# Posibus.net
KiCad netlist of a schematic drawn in EAGLE
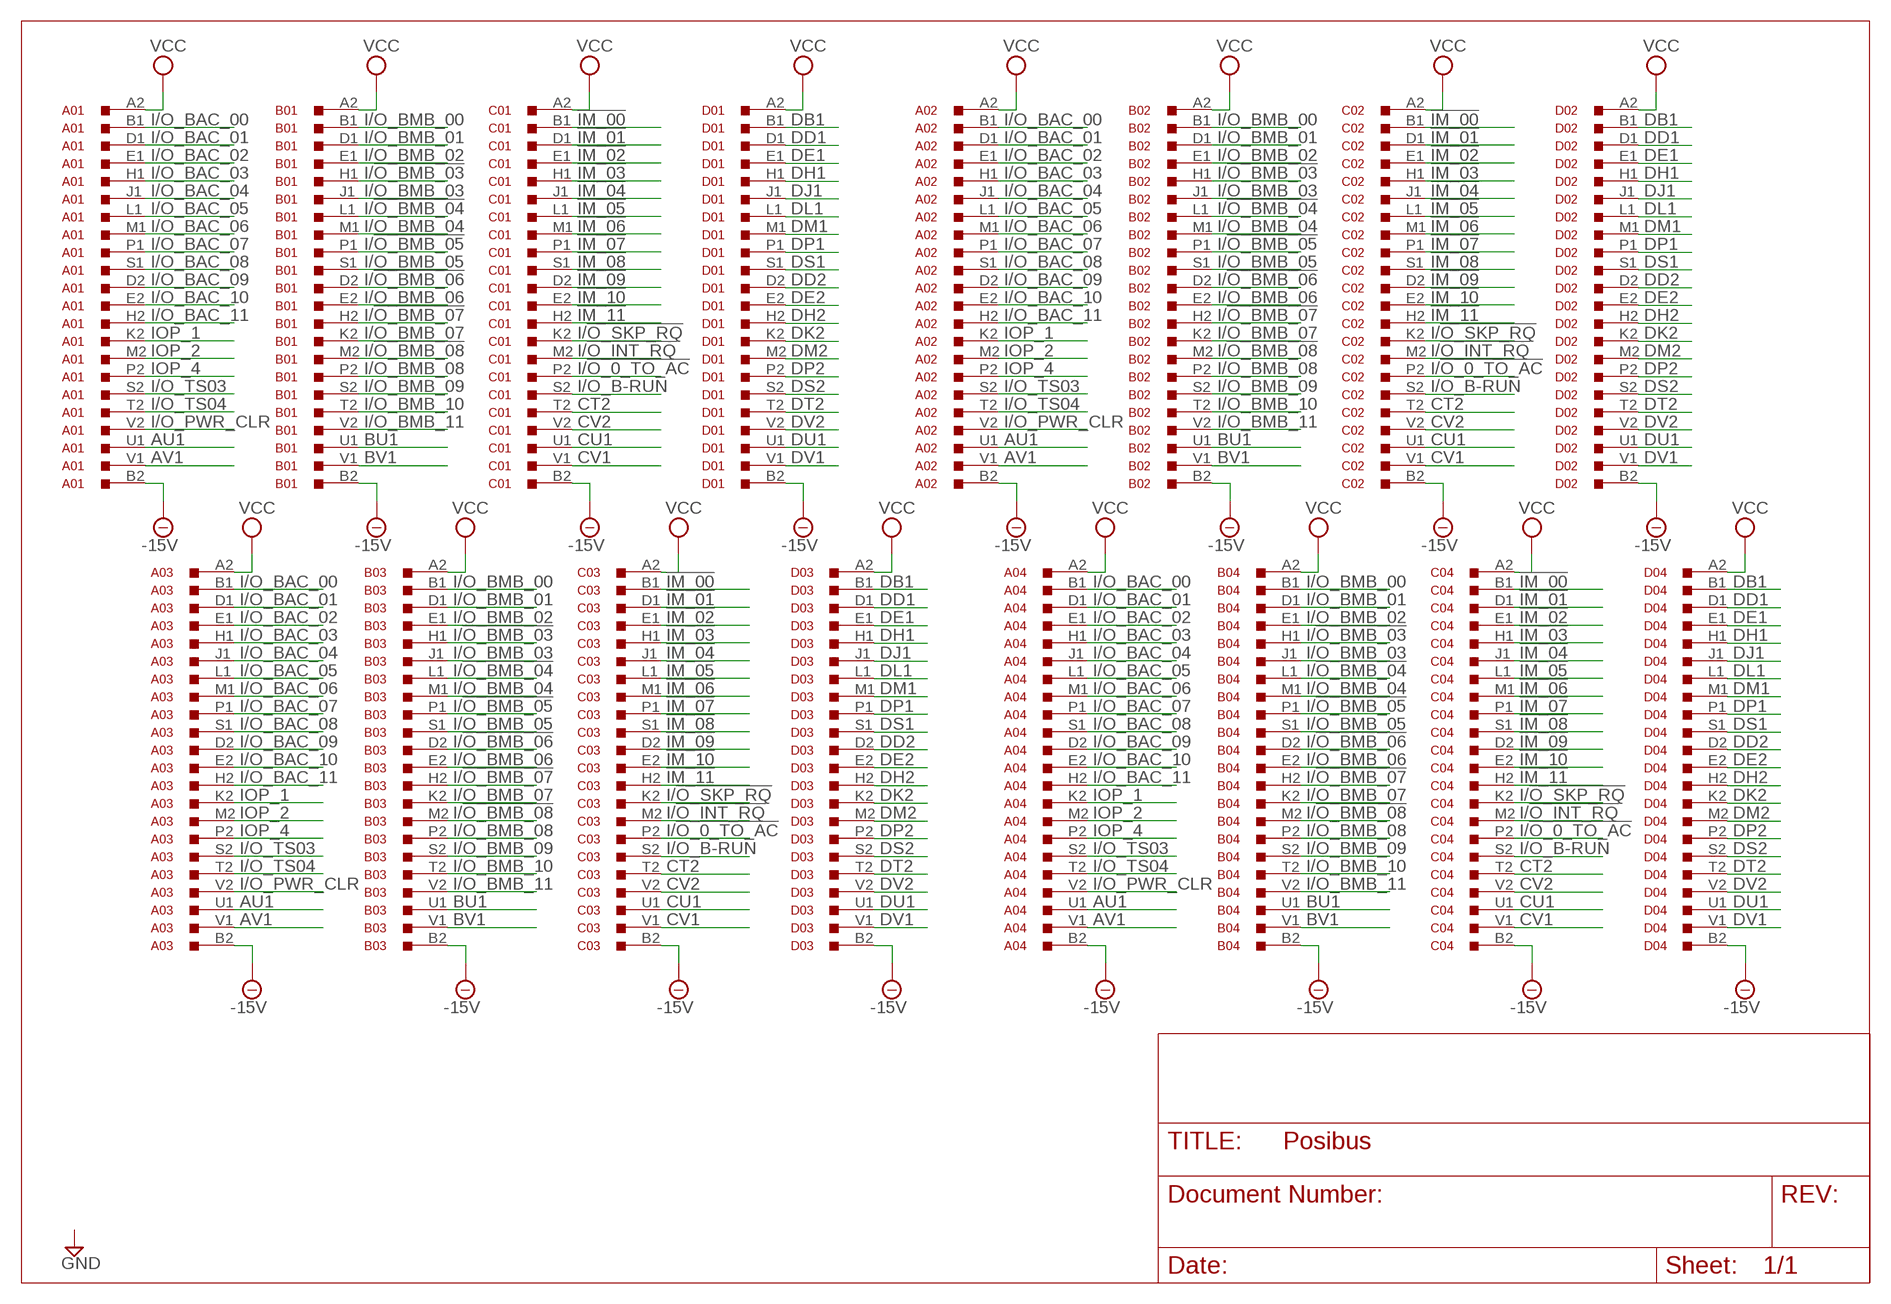
[diagram p0: schematic, sheet 1]

(export (version "E")
  (design (tool "Eeschema 10.0.6"))
  (components
    (comp (ref "A01")
      (value "M903")
      (footprint "eagle-import:H807")
      (libsource (lib "eagle-import") (part "M903"))
    )
    (comp (ref "A02")
      (value "M903")
      (footprint "eagle-import:H807")
      (libsource (lib "eagle-import") (part "M903"))
    )
    (comp (ref "A03")
      (value "M903")
      (footprint "eagle-import:H807")
      (libsource (lib "eagle-import") (part "M903"))
    )
    (comp (ref "A04")
      (value "M903")
      (footprint "eagle-import:H807")
      (libsource (lib "eagle-import") (part "M903"))
    )
    (comp (ref "B01")
      (value "M903")
      (footprint "eagle-import:H807")
      (libsource (lib "eagle-import") (part "M903"))
    )
    (comp (ref "B02")
      (value "M903")
      (footprint "eagle-import:H807")
      (libsource (lib "eagle-import") (part "M903"))
    )
    (comp (ref "B03")
      (value "M903")
      (footprint "eagle-import:H807")
      (libsource (lib "eagle-import") (part "M903"))
    )
    (comp (ref "B04")
      (value "M903")
      (footprint "eagle-import:H807")
      (libsource (lib "eagle-import") (part "M903"))
    )
    (comp (ref "C01")
      (value "M903")
      (footprint "eagle-import:H807")
      (libsource (lib "eagle-import") (part "M903"))
    )
    (comp (ref "C02")
      (value "M903")
      (footprint "eagle-import:H807")
      (libsource (lib "eagle-import") (part "M903"))
    )
    (comp (ref "C03")
      (value "M903")
      (footprint "eagle-import:H807")
      (libsource (lib "eagle-import") (part "M903"))
    )
    (comp (ref "C04")
      (value "M903")
      (footprint "eagle-import:H807")
      (libsource (lib "eagle-import") (part "M903"))
    )
    (comp (ref "D01")
      (value "M903")
      (footprint "eagle-import:H807")
      (libsource (lib "eagle-import") (part "M903"))
    )
    (comp (ref "D02")
      (value "M903")
      (footprint "eagle-import:H807")
      (libsource (lib "eagle-import") (part "M903"))
    )
    (comp (ref "D03")
      (value "M903")
      (footprint "eagle-import:H807")
      (libsource (lib "eagle-import") (part "M903"))
    )
    (comp (ref "D04")
      (value "M903")
      (footprint "eagle-import:H807")
      (libsource (lib "eagle-import") (part "M903"))
    )
  )
  (nets
    (net (code "1") (name "-15V") (class "Default")
      (node (ref "A01") (pin "B2") (pinfunction "P$2_B2") (pintype "bidirectional"))
      (node (ref "A02") (pin "B2") (pinfunction "P$2_B2") (pintype "bidirectional"))
      (node (ref "A03") (pin "B2") (pinfunction "P$2_B2") (pintype "bidirectional"))
      (node (ref "A04") (pin "B2") (pinfunction "P$2_B2") (pintype "bidirectional"))
      (node (ref "B01") (pin "B2") (pinfunction "P$2_B2") (pintype "bidirectional"))
      (node (ref "B02") (pin "B2") (pinfunction "P$2_B2") (pintype "bidirectional"))
      (node (ref "B03") (pin "B2") (pinfunction "P$2_B2") (pintype "bidirectional"))
      (node (ref "B04") (pin "B2") (pinfunction "P$2_B2") (pintype "bidirectional"))
      (node (ref "C01") (pin "B2") (pinfunction "P$2_B2") (pintype "bidirectional"))
      (node (ref "C02") (pin "B2") (pinfunction "P$2_B2") (pintype "bidirectional"))
      (node (ref "C03") (pin "B2") (pinfunction "P$2_B2") (pintype "bidirectional"))
      (node (ref "C04") (pin "B2") (pinfunction "P$2_B2") (pintype "bidirectional"))
      (node (ref "D01") (pin "B2") (pinfunction "P$2_B2") (pintype "bidirectional"))
      (node (ref "D02") (pin "B2") (pinfunction "P$2_B2") (pintype "bidirectional"))
      (node (ref "D03") (pin "B2") (pinfunction "P$2_B2") (pintype "bidirectional"))
      (node (ref "D04") (pin "B2") (pinfunction "P$2_B2") (pintype "bidirectional"))
    )
    (net (code "2") (name "/AU1") (class "Default")
      (node (ref "A01") (pin "U1") (pinfunction "P$2_U1") (pintype "bidirectional"))
      (node (ref "A02") (pin "U1") (pinfunction "P$2_U1") (pintype "bidirectional"))
      (node (ref "A03") (pin "U1") (pinfunction "P$2_U1") (pintype "bidirectional"))
      (node (ref "A04") (pin "U1") (pinfunction "P$2_U1") (pintype "bidirectional"))
    )
    (net (code "3") (name "/AV1") (class "Default")
      (node (ref "A01") (pin "V1") (pinfunction "P$2_V1") (pintype "bidirectional"))
      (node (ref "A02") (pin "V1") (pinfunction "P$2_V1") (pintype "bidirectional"))
      (node (ref "A03") (pin "V1") (pinfunction "P$2_V1") (pintype "bidirectional"))
      (node (ref "A04") (pin "V1") (pinfunction "P$2_V1") (pintype "bidirectional"))
    )
    (net (code "4") (name "/BU1") (class "Default")
      (node (ref "B01") (pin "U1") (pinfunction "P$2_U1") (pintype "bidirectional"))
      (node (ref "B02") (pin "U1") (pinfunction "P$2_U1") (pintype "bidirectional"))
      (node (ref "B03") (pin "U1") (pinfunction "P$2_U1") (pintype "bidirectional"))
      (node (ref "B04") (pin "U1") (pinfunction "P$2_U1") (pintype "bidirectional"))
    )
    (net (code "5") (name "/BV1") (class "Default")
      (node (ref "B01") (pin "V1") (pinfunction "P$2_V1") (pintype "bidirectional"))
      (node (ref "B02") (pin "V1") (pinfunction "P$2_V1") (pintype "bidirectional"))
      (node (ref "B03") (pin "V1") (pinfunction "P$2_V1") (pintype "bidirectional"))
      (node (ref "B04") (pin "V1") (pinfunction "P$2_V1") (pintype "bidirectional"))
    )
    (net (code "6") (name "/CT2") (class "Default")
      (node (ref "C01") (pin "T2") (pinfunction "P$2_T2") (pintype "bidirectional"))
      (node (ref "C02") (pin "T2") (pinfunction "P$2_T2") (pintype "bidirectional"))
      (node (ref "C03") (pin "T2") (pinfunction "P$2_T2") (pintype "bidirectional"))
      (node (ref "C04") (pin "T2") (pinfunction "P$2_T2") (pintype "bidirectional"))
    )
    (net (code "7") (name "/CU1") (class "Default")
      (node (ref "C01") (pin "U1") (pinfunction "P$2_U1") (pintype "bidirectional"))
      (node (ref "C02") (pin "U1") (pinfunction "P$2_U1") (pintype "bidirectional"))
      (node (ref "C03") (pin "U1") (pinfunction "P$2_U1") (pintype "bidirectional"))
      (node (ref "C04") (pin "U1") (pinfunction "P$2_U1") (pintype "bidirectional"))
    )
    (net (code "8") (name "/CV1") (class "Default")
      (node (ref "C01") (pin "V1") (pinfunction "P$2_V1") (pintype "bidirectional"))
      (node (ref "C02") (pin "V1") (pinfunction "P$2_V1") (pintype "bidirectional"))
      (node (ref "C03") (pin "V1") (pinfunction "P$2_V1") (pintype "bidirectional"))
      (node (ref "C04") (pin "V1") (pinfunction "P$2_V1") (pintype "bidirectional"))
    )
    (net (code "9") (name "/CV2") (class "Default")
      (node (ref "C01") (pin "V2") (pinfunction "P$2_V2") (pintype "bidirectional"))
      (node (ref "C02") (pin "V2") (pinfunction "P$2_V2") (pintype "bidirectional"))
      (node (ref "C03") (pin "V2") (pinfunction "P$2_V2") (pintype "bidirectional"))
      (node (ref "C04") (pin "V2") (pinfunction "P$2_V2") (pintype "bidirectional"))
    )
    (net (code "10") (name "/DB1") (class "Default")
      (node (ref "D01") (pin "B1") (pinfunction "P$2_B1") (pintype "bidirectional"))
      (node (ref "D02") (pin "B1") (pinfunction "P$2_B1") (pintype "bidirectional"))
      (node (ref "D03") (pin "B1") (pinfunction "P$2_B1") (pintype "bidirectional"))
      (node (ref "D04") (pin "B1") (pinfunction "P$2_B1") (pintype "bidirectional"))
    )
    (net (code "11") (name "/DD1") (class "Default")
      (node (ref "D01") (pin "D1") (pinfunction "P$2_D1") (pintype "bidirectional"))
      (node (ref "D02") (pin "D1") (pinfunction "P$2_D1") (pintype "bidirectional"))
      (node (ref "D03") (pin "D1") (pinfunction "P$2_D1") (pintype "bidirectional"))
      (node (ref "D04") (pin "D1") (pinfunction "P$2_D1") (pintype "bidirectional"))
    )
    (net (code "12") (name "/DD2") (class "Default")
      (node (ref "D01") (pin "D2") (pinfunction "P$2_D2") (pintype "bidirectional"))
      (node (ref "D02") (pin "D2") (pinfunction "P$2_D2") (pintype "bidirectional"))
      (node (ref "D03") (pin "D2") (pinfunction "P$2_D2") (pintype "bidirectional"))
      (node (ref "D04") (pin "D2") (pinfunction "P$2_D2") (pintype "bidirectional"))
    )
    (net (code "13") (name "/DE1") (class "Default")
      (node (ref "D01") (pin "E1") (pinfunction "P$2_E1") (pintype "bidirectional"))
      (node (ref "D02") (pin "E1") (pinfunction "P$2_E1") (pintype "bidirectional"))
      (node (ref "D03") (pin "E1") (pinfunction "P$2_E1") (pintype "bidirectional"))
      (node (ref "D04") (pin "E1") (pinfunction "P$2_E1") (pintype "bidirectional"))
    )
    (net (code "14") (name "/DE2") (class "Default")
      (node (ref "D01") (pin "E2") (pinfunction "P$2_E2") (pintype "bidirectional"))
      (node (ref "D02") (pin "E2") (pinfunction "P$2_E2") (pintype "bidirectional"))
      (node (ref "D03") (pin "E2") (pinfunction "P$2_E2") (pintype "bidirectional"))
      (node (ref "D04") (pin "E2") (pinfunction "P$2_E2") (pintype "bidirectional"))
    )
    (net (code "15") (name "/DH1") (class "Default")
      (node (ref "D01") (pin "H1") (pinfunction "P$2_H1") (pintype "bidirectional"))
      (node (ref "D02") (pin "H1") (pinfunction "P$2_H1") (pintype "bidirectional"))
      (node (ref "D03") (pin "H1") (pinfunction "P$2_H1") (pintype "bidirectional"))
      (node (ref "D04") (pin "H1") (pinfunction "P$2_H1") (pintype "bidirectional"))
    )
    (net (code "16") (name "/DH2") (class "Default")
      (node (ref "D01") (pin "H2") (pinfunction "P$2_H2") (pintype "bidirectional"))
      (node (ref "D02") (pin "H2") (pinfunction "P$2_H2") (pintype "bidirectional"))
      (node (ref "D03") (pin "H2") (pinfunction "P$2_H2") (pintype "bidirectional"))
      (node (ref "D04") (pin "H2") (pinfunction "P$2_H2") (pintype "bidirectional"))
    )
    (net (code "17") (name "/DJ1") (class "Default")
      (node (ref "D01") (pin "J1") (pinfunction "P$2_J1") (pintype "bidirectional"))
      (node (ref "D02") (pin "J1") (pinfunction "P$2_J1") (pintype "bidirectional"))
      (node (ref "D03") (pin "J1") (pinfunction "P$2_J1") (pintype "bidirectional"))
      (node (ref "D04") (pin "J1") (pinfunction "P$2_J1") (pintype "bidirectional"))
    )
    (net (code "18") (name "/DK2") (class "Default")
      (node (ref "D01") (pin "K2") (pinfunction "P$2_K2") (pintype "bidirectional"))
      (node (ref "D02") (pin "K2") (pinfunction "P$2_K2") (pintype "bidirectional"))
      (node (ref "D03") (pin "K2") (pinfunction "P$2_K2") (pintype "bidirectional"))
      (node (ref "D04") (pin "K2") (pinfunction "P$2_K2") (pintype "bidirectional"))
    )
    (net (code "19") (name "/DL1") (class "Default")
      (node (ref "D01") (pin "L1") (pinfunction "P$2_L1") (pintype "bidirectional"))
      (node (ref "D02") (pin "L1") (pinfunction "P$2_L1") (pintype "bidirectional"))
      (node (ref "D03") (pin "L1") (pinfunction "P$2_L1") (pintype "bidirectional"))
      (node (ref "D04") (pin "L1") (pinfunction "P$2_L1") (pintype "bidirectional"))
    )
    (net (code "20") (name "/DM1") (class "Default")
      (node (ref "D01") (pin "M1") (pinfunction "P$2_M1") (pintype "bidirectional"))
      (node (ref "D02") (pin "M1") (pinfunction "P$2_M1") (pintype "bidirectional"))
      (node (ref "D03") (pin "M1") (pinfunction "P$2_M1") (pintype "bidirectional"))
      (node (ref "D04") (pin "M1") (pinfunction "P$2_M1") (pintype "bidirectional"))
    )
    (net (code "21") (name "/DM2") (class "Default")
      (node (ref "D01") (pin "M2") (pinfunction "P$2_M2") (pintype "bidirectional"))
      (node (ref "D02") (pin "M2") (pinfunction "P$2_M2") (pintype "bidirectional"))
      (node (ref "D03") (pin "M2") (pinfunction "P$2_M2") (pintype "bidirectional"))
      (node (ref "D04") (pin "M2") (pinfunction "P$2_M2") (pintype "bidirectional"))
    )
    (net (code "22") (name "/DP1") (class "Default")
      (node (ref "D01") (pin "P1") (pinfunction "P$2_P1") (pintype "bidirectional"))
      (node (ref "D02") (pin "P1") (pinfunction "P$2_P1") (pintype "bidirectional"))
      (node (ref "D03") (pin "P1") (pinfunction "P$2_P1") (pintype "bidirectional"))
      (node (ref "D04") (pin "P1") (pinfunction "P$2_P1") (pintype "bidirectional"))
    )
    (net (code "23") (name "/DP2") (class "Default")
      (node (ref "D01") (pin "P2") (pinfunction "P$2_P2") (pintype "bidirectional"))
      (node (ref "D02") (pin "P2") (pinfunction "P$2_P2") (pintype "bidirectional"))
      (node (ref "D03") (pin "P2") (pinfunction "P$2_P2") (pintype "bidirectional"))
      (node (ref "D04") (pin "P2") (pinfunction "P$2_P2") (pintype "bidirectional"))
    )
    (net (code "24") (name "/DS1") (class "Default")
      (node (ref "D01") (pin "S1") (pinfunction "P$2_S1") (pintype "bidirectional"))
      (node (ref "D02") (pin "S1") (pinfunction "P$2_S1") (pintype "bidirectional"))
      (node (ref "D03") (pin "S1") (pinfunction "P$2_S1") (pintype "bidirectional"))
      (node (ref "D04") (pin "S1") (pinfunction "P$2_S1") (pintype "bidirectional"))
    )
    (net (code "25") (name "/DS2") (class "Default")
      (node (ref "D01") (pin "S2") (pinfunction "P$2_S2") (pintype "bidirectional"))
      (node (ref "D02") (pin "S2") (pinfunction "P$2_S2") (pintype "bidirectional"))
      (node (ref "D03") (pin "S2") (pinfunction "P$2_S2") (pintype "bidirectional"))
      (node (ref "D04") (pin "S2") (pinfunction "P$2_S2") (pintype "bidirectional"))
    )
    (net (code "26") (name "/DT2") (class "Default")
      (node (ref "D01") (pin "T2") (pinfunction "P$2_T2") (pintype "bidirectional"))
      (node (ref "D02") (pin "T2") (pinfunction "P$2_T2") (pintype "bidirectional"))
      (node (ref "D03") (pin "T2") (pinfunction "P$2_T2") (pintype "bidirectional"))
      (node (ref "D04") (pin "T2") (pinfunction "P$2_T2") (pintype "bidirectional"))
    )
    (net (code "27") (name "/DU1") (class "Default")
      (node (ref "D01") (pin "U1") (pinfunction "P$2_U1") (pintype "bidirectional"))
      (node (ref "D02") (pin "U1") (pinfunction "P$2_U1") (pintype "bidirectional"))
      (node (ref "D03") (pin "U1") (pinfunction "P$2_U1") (pintype "bidirectional"))
      (node (ref "D04") (pin "U1") (pinfunction "P$2_U1") (pintype "bidirectional"))
    )
    (net (code "28") (name "/DV1") (class "Default")
      (node (ref "D01") (pin "V1") (pinfunction "P$2_V1") (pintype "bidirectional"))
      (node (ref "D02") (pin "V1") (pinfunction "P$2_V1") (pintype "bidirectional"))
      (node (ref "D03") (pin "V1") (pinfunction "P$2_V1") (pintype "bidirectional"))
      (node (ref "D04") (pin "V1") (pinfunction "P$2_V1") (pintype "bidirectional"))
    )
    (net (code "29") (name "/DV2") (class "Default")
      (node (ref "D01") (pin "V2") (pinfunction "P$2_V2") (pintype "bidirectional"))
      (node (ref "D02") (pin "V2") (pinfunction "P$2_V2") (pintype "bidirectional"))
      (node (ref "D03") (pin "V2") (pinfunction "P$2_V2") (pintype "bidirectional"))
      (node (ref "D04") (pin "V2") (pinfunction "P$2_V2") (pintype "bidirectional"))
    )
    (net (code "30") (name "/IOP_1") (class "Default")
      (node (ref "A01") (pin "K2") (pinfunction "P$2_K2") (pintype "bidirectional"))
      (node (ref "A02") (pin "K2") (pinfunction "P$2_K2") (pintype "bidirectional"))
      (node (ref "A03") (pin "K2") (pinfunction "P$2_K2") (pintype "bidirectional"))
      (node (ref "A04") (pin "K2") (pinfunction "P$2_K2") (pintype "bidirectional"))
    )
    (net (code "31") (name "/IOP_2") (class "Default")
      (node (ref "A01") (pin "M2") (pinfunction "P$2_M2") (pintype "bidirectional"))
      (node (ref "A02") (pin "M2") (pinfunction "P$2_M2") (pintype "bidirectional"))
      (node (ref "A03") (pin "M2") (pinfunction "P$2_M2") (pintype "bidirectional"))
      (node (ref "A04") (pin "M2") (pinfunction "P$2_M2") (pintype "bidirectional"))
    )
    (net (code "32") (name "/IOP_4") (class "Default")
      (node (ref "A01") (pin "P2") (pinfunction "P$2_P2") (pintype "bidirectional"))
      (node (ref "A02") (pin "P2") (pinfunction "P$2_P2") (pintype "bidirectional"))
      (node (ref "A03") (pin "P2") (pinfunction "P$2_P2") (pintype "bidirectional"))
      (node (ref "A04") (pin "P2") (pinfunction "P$2_P2") (pintype "bidirectional"))
    )
    (net (code "33") (name "/I{slash}O_B-RUN") (class "Default")
      (node (ref "C01") (pin "S2") (pinfunction "P$2_S2") (pintype "bidirectional"))
      (node (ref "C02") (pin "S2") (pinfunction "P$2_S2") (pintype "bidirectional"))
      (node (ref "C03") (pin "S2") (pinfunction "P$2_S2") (pintype "bidirectional"))
      (node (ref "C04") (pin "S2") (pinfunction "P$2_S2") (pintype "bidirectional"))
    )
    (net (code "34") (name "/I{slash}O_BAC_00") (class "Default")
      (node (ref "A01") (pin "B1") (pinfunction "P$2_B1") (pintype "bidirectional"))
      (node (ref "A02") (pin "B1") (pinfunction "P$2_B1") (pintype "bidirectional"))
      (node (ref "A03") (pin "B1") (pinfunction "P$2_B1") (pintype "bidirectional"))
      (node (ref "A04") (pin "B1") (pinfunction "P$2_B1") (pintype "bidirectional"))
    )
    (net (code "35") (name "/I{slash}O_BAC_01") (class "Default")
      (node (ref "A01") (pin "D1") (pinfunction "P$2_D1") (pintype "bidirectional"))
      (node (ref "A02") (pin "D1") (pinfunction "P$2_D1") (pintype "bidirectional"))
      (node (ref "A03") (pin "D1") (pinfunction "P$2_D1") (pintype "bidirectional"))
      (node (ref "A04") (pin "D1") (pinfunction "P$2_D1") (pintype "bidirectional"))
    )
    (net (code "36") (name "/I{slash}O_BAC_02") (class "Default")
      (node (ref "A01") (pin "E1") (pinfunction "P$2_E1") (pintype "bidirectional"))
      (node (ref "A02") (pin "E1") (pinfunction "P$2_E1") (pintype "bidirectional"))
      (node (ref "A03") (pin "E1") (pinfunction "P$2_E1") (pintype "bidirectional"))
      (node (ref "A04") (pin "E1") (pinfunction "P$2_E1") (pintype "bidirectional"))
    )
    (net (code "37") (name "/I{slash}O_BAC_03") (class "Default")
      (node (ref "A01") (pin "H1") (pinfunction "P$2_H1") (pintype "bidirectional"))
      (node (ref "A02") (pin "H1") (pinfunction "P$2_H1") (pintype "bidirectional"))
      (node (ref "A03") (pin "H1") (pinfunction "P$2_H1") (pintype "bidirectional"))
      (node (ref "A04") (pin "H1") (pinfunction "P$2_H1") (pintype "bidirectional"))
    )
    (net (code "38") (name "/I{slash}O_BAC_04") (class "Default")
      (node (ref "A01") (pin "J1") (pinfunction "P$2_J1") (pintype "bidirectional"))
      (node (ref "A02") (pin "J1") (pinfunction "P$2_J1") (pintype "bidirectional"))
      (node (ref "A03") (pin "J1") (pinfunction "P$2_J1") (pintype "bidirectional"))
      (node (ref "A04") (pin "J1") (pinfunction "P$2_J1") (pintype "bidirectional"))
    )
    (net (code "39") (name "/I{slash}O_BAC_05") (class "Default")
      (node (ref "A01") (pin "L1") (pinfunction "P$2_L1") (pintype "bidirectional"))
      (node (ref "A02") (pin "L1") (pinfunction "P$2_L1") (pintype "bidirectional"))
      (node (ref "A03") (pin "L1") (pinfunction "P$2_L1") (pintype "bidirectional"))
      (node (ref "A04") (pin "L1") (pinfunction "P$2_L1") (pintype "bidirectional"))
    )
    (net (code "40") (name "/I{slash}O_BAC_06") (class "Default")
      (node (ref "A01") (pin "M1") (pinfunction "P$2_M1") (pintype "bidirectional"))
      (node (ref "A02") (pin "M1") (pinfunction "P$2_M1") (pintype "bidirectional"))
      (node (ref "A03") (pin "M1") (pinfunction "P$2_M1") (pintype "bidirectional"))
      (node (ref "A04") (pin "M1") (pinfunction "P$2_M1") (pintype "bidirectional"))
    )
    (net (code "41") (name "/I{slash}O_BAC_07") (class "Default")
      (node (ref "A01") (pin "P1") (pinfunction "P$2_P1") (pintype "bidirectional"))
      (node (ref "A02") (pin "P1") (pinfunction "P$2_P1") (pintype "bidirectional"))
      (node (ref "A03") (pin "P1") (pinfunction "P$2_P1") (pintype "bidirectional"))
      (node (ref "A04") (pin "P1") (pinfunction "P$2_P1") (pintype "bidirectional"))
    )
    (net (code "42") (name "/I{slash}O_BAC_08") (class "Default")
      (node (ref "A01") (pin "S1") (pinfunction "P$2_S1") (pintype "bidirectional"))
      (node (ref "A02") (pin "S1") (pinfunction "P$2_S1") (pintype "bidirectional"))
      (node (ref "A03") (pin "S1") (pinfunction "P$2_S1") (pintype "bidirectional"))
      (node (ref "A04") (pin "S1") (pinfunction "P$2_S1") (pintype "bidirectional"))
    )
    (net (code "43") (name "/I{slash}O_BAC_09") (class "Default")
      (node (ref "A01") (pin "D2") (pinfunction "P$2_D2") (pintype "bidirectional"))
      (node (ref "A02") (pin "D2") (pinfunction "P$2_D2") (pintype "bidirectional"))
      (node (ref "A03") (pin "D2") (pinfunction "P$2_D2") (pintype "bidirectional"))
      (node (ref "A04") (pin "D2") (pinfunction "P$2_D2") (pintype "bidirectional"))
    )
    (net (code "44") (name "/I{slash}O_BAC_10") (class "Default")
      (node (ref "A01") (pin "E2") (pinfunction "P$2_E2") (pintype "bidirectional"))
      (node (ref "A02") (pin "E2") (pinfunction "P$2_E2") (pintype "bidirectional"))
      (node (ref "A03") (pin "E2") (pinfunction "P$2_E2") (pintype "bidirectional"))
      (node (ref "A04") (pin "E2") (pinfunction "P$2_E2") (pintype "bidirectional"))
    )
    (net (code "45") (name "/I{slash}O_BAC_11") (class "Default")
      (node (ref "A01") (pin "H2") (pinfunction "P$2_H2") (pintype "bidirectional"))
      (node (ref "A02") (pin "H2") (pinfunction "P$2_H2") (pintype "bidirectional"))
      (node (ref "A03") (pin "H2") (pinfunction "P$2_H2") (pintype "bidirectional"))
      (node (ref "A04") (pin "H2") (pinfunction "P$2_H2") (pintype "bidirectional"))
    )
    (net (code "46") (name "/I{slash}O_BMB_00") (class "Default")
      (node (ref "B01") (pin "B1") (pinfunction "P$2_B1") (pintype "bidirectional"))
      (node (ref "B02") (pin "B1") (pinfunction "P$2_B1") (pintype "bidirectional"))
      (node (ref "B03") (pin "B1") (pinfunction "P$2_B1") (pintype "bidirectional"))
      (node (ref "B04") (pin "B1") (pinfunction "P$2_B1") (pintype "bidirectional"))
    )
    (net (code "47") (name "/I{slash}O_BMB_01") (class "Default")
      (node (ref "B01") (pin "D1") (pinfunction "P$2_D1") (pintype "bidirectional"))
      (node (ref "B02") (pin "D1") (pinfunction "P$2_D1") (pintype "bidirectional"))
      (node (ref "B03") (pin "D1") (pinfunction "P$2_D1") (pintype "bidirectional"))
      (node (ref "B04") (pin "D1") (pinfunction "P$2_D1") (pintype "bidirectional"))
    )
    (net (code "48") (name "/I{slash}O_BMB_02") (class "Default")
      (node (ref "B01") (pin "E1") (pinfunction "P$2_E1") (pintype "bidirectional"))
      (node (ref "B02") (pin "E1") (pinfunction "P$2_E1") (pintype "bidirectional"))
      (node (ref "B03") (pin "E1") (pinfunction "P$2_E1") (pintype "bidirectional"))
      (node (ref "B04") (pin "E1") (pinfunction "P$2_E1") (pintype "bidirectional"))
    )
    (net (code "49") (name "/I{slash}O_BMB_03") (class "Default")
      (node (ref "B01") (pin "J1") (pinfunction "P$2_J1") (pintype "bidirectional"))
      (node (ref "B02") (pin "J1") (pinfunction "P$2_J1") (pintype "bidirectional"))
      (node (ref "B03") (pin "J1") (pinfunction "P$2_J1") (pintype "bidirectional"))
      (node (ref "B04") (pin "J1") (pinfunction "P$2_J1") (pintype "bidirectional"))
    )
    (net (code "50") (name "/I{slash}O_BMB_04") (class "Default")
      (node (ref "B01") (pin "M1") (pinfunction "P$2_M1") (pintype "bidirectional"))
      (node (ref "B02") (pin "M1") (pinfunction "P$2_M1") (pintype "bidirectional"))
      (node (ref "B03") (pin "M1") (pinfunction "P$2_M1") (pintype "bidirectional"))
      (node (ref "B04") (pin "M1") (pinfunction "P$2_M1") (pintype "bidirectional"))
    )
    (net (code "51") (name "/I{slash}O_BMB_05") (class "Default")
      (node (ref "B01") (pin "S1") (pinfunction "P$2_S1") (pintype "bidirectional"))
      (node (ref "B02") (pin "S1") (pinfunction "P$2_S1") (pintype "bidirectional"))
      (node (ref "B03") (pin "S1") (pinfunction "P$2_S1") (pintype "bidirectional"))
      (node (ref "B04") (pin "S1") (pinfunction "P$2_S1") (pintype "bidirectional"))
    )
    (net (code "52") (name "/I{slash}O_BMB_06") (class "Default")
      (node (ref "B01") (pin "E2") (pinfunction "P$2_E2") (pintype "bidirectional"))
      (node (ref "B02") (pin "E2") (pinfunction "P$2_E2") (pintype "bidirectional"))
      (node (ref "B03") (pin "E2") (pinfunction "P$2_E2") (pintype "bidirectional"))
      (node (ref "B04") (pin "E2") (pinfunction "P$2_E2") (pintype "bidirectional"))
    )
    (net (code "53") (name "/I{slash}O_BMB_07") (class "Default")
      (node (ref "B01") (pin "K2") (pinfunction "P$2_K2") (pintype "bidirectional"))
      (node (ref "B02") (pin "K2") (pinfunction "P$2_K2") (pintype "bidirectional"))
      (node (ref "B03") (pin "K2") (pinfunction "P$2_K2") (pintype "bidirectional"))
      (node (ref "B04") (pin "K2") (pinfunction "P$2_K2") (pintype "bidirectional"))
    )
    (net (code "54") (name "/I{slash}O_BMB_08") (class "Default")
      (node (ref "B01") (pin "P2") (pinfunction "P$2_P2") (pintype "bidirectional"))
      (node (ref "B02") (pin "P2") (pinfunction "P$2_P2") (pintype "bidirectional"))
      (node (ref "B03") (pin "P2") (pinfunction "P$2_P2") (pintype "bidirectional"))
      (node (ref "B04") (pin "P2") (pinfunction "P$2_P2") (pintype "bidirectional"))
    )
    (net (code "55") (name "/I{slash}O_BMB_09") (class "Default")
      (node (ref "B01") (pin "S2") (pinfunction "P$2_S2") (pintype "bidirectional"))
      (node (ref "B02") (pin "S2") (pinfunction "P$2_S2") (pintype "bidirectional"))
      (node (ref "B03") (pin "S2") (pinfunction "P$2_S2") (pintype "bidirectional"))
      (node (ref "B04") (pin "S2") (pinfunction "P$2_S2") (pintype "bidirectional"))
    )
    (net (code "56") (name "/I{slash}O_BMB_10") (class "Default")
      (node (ref "B01") (pin "T2") (pinfunction "P$2_T2") (pintype "bidirectional"))
      (node (ref "B02") (pin "T2") (pinfunction "P$2_T2") (pintype "bidirectional"))
      (node (ref "B03") (pin "T2") (pinfunction "P$2_T2") (pintype "bidirectional"))
      (node (ref "B04") (pin "T2") (pinfunction "P$2_T2") (pintype "bidirectional"))
    )
    (net (code "57") (name "/I{slash}O_BMB_11") (class "Default")
      (node (ref "B01") (pin "V2") (pinfunction "P$2_V2") (pintype "bidirectional"))
      (node (ref "B02") (pin "V2") (pinfunction "P$2_V2") (pintype "bidirectional"))
      (node (ref "B03") (pin "V2") (pinfunction "P$2_V2") (pintype "bidirectional"))
      (node (ref "B04") (pin "V2") (pinfunction "P$2_V2") (pintype "bidirectional"))
    )
    (net (code "58") (name "/I{slash}O_PWR_CLR") (class "Default")
      (node (ref "A01") (pin "V2") (pinfunction "P$2_V2") (pintype "bidirectional"))
      (node (ref "A02") (pin "V2") (pinfunction "P$2_V2") (pintype "bidirectional"))
      (node (ref "A03") (pin "V2") (pinfunction "P$2_V2") (pintype "bidirectional"))
      (node (ref "A04") (pin "V2") (pinfunction "P$2_V2") (pintype "bidirectional"))
    )
    (net (code "59") (name "/I{slash}O_TS03") (class "Default")
      (node (ref "A01") (pin "S2") (pinfunction "P$2_S2") (pintype "bidirectional"))
      (node (ref "A02") (pin "S2") (pinfunction "P$2_S2") (pintype "bidirectional"))
      (node (ref "A03") (pin "S2") (pinfunction "P$2_S2") (pintype "bidirectional"))
      (node (ref "A04") (pin "S2") (pinfunction "P$2_S2") (pintype "bidirectional"))
    )
    (net (code "60") (name "/I{slash}O_TS04") (class "Default")
      (node (ref "A01") (pin "T2") (pinfunction "P$2_T2") (pintype "bidirectional"))
      (node (ref "A02") (pin "T2") (pinfunction "P$2_T2") (pintype "bidirectional"))
      (node (ref "A03") (pin "T2") (pinfunction "P$2_T2") (pintype "bidirectional"))
      (node (ref "A04") (pin "T2") (pinfunction "P$2_T2") (pintype "bidirectional"))
    )
    (net (code "61") (name "/I{slash}~{O_0_TO_AC}") (class "Default")
      (node (ref "C01") (pin "P2") (pinfunction "P$2_P2") (pintype "bidirectional"))
      (node (ref "C02") (pin "P2") (pinfunction "P$2_P2") (pintype "bidirectional"))
      (node (ref "C03") (pin "P2") (pinfunction "P$2_P2") (pintype "bidirectional"))
      (node (ref "C04") (pin "P2") (pinfunction "P$2_P2") (pintype "bidirectional"))
    )
    (net (code "62") (name "/I{slash}~{O_BMB_03}") (class "Default")
      (node (ref "B01") (pin "H1") (pinfunction "P$2_H1") (pintype "bidirectional"))
      (node (ref "B02") (pin "H1") (pinfunction "P$2_H1") (pintype "bidirectional"))
      (node (ref "B03") (pin "H1") (pinfunction "P$2_H1") (pintype "bidirectional"))
      (node (ref "B04") (pin "H1") (pinfunction "P$2_H1") (pintype "bidirectional"))
    )
    (net (code "63") (name "/I{slash}~{O_BMB_04}") (class "Default")
      (node (ref "B01") (pin "L1") (pinfunction "P$2_L1") (pintype "bidirectional"))
      (node (ref "B02") (pin "L1") (pinfunction "P$2_L1") (pintype "bidirectional"))
      (node (ref "B03") (pin "L1") (pinfunction "P$2_L1") (pintype "bidirectional"))
      (node (ref "B04") (pin "L1") (pinfunction "P$2_L1") (pintype "bidirectional"))
    )
    (net (code "64") (name "/I{slash}~{O_BMB_05}") (class "Default")
      (node (ref "B01") (pin "P1") (pinfunction "P$2_P1") (pintype "bidirectional"))
      (node (ref "B02") (pin "P1") (pinfunction "P$2_P1") (pintype "bidirectional"))
      (node (ref "B03") (pin "P1") (pinfunction "P$2_P1") (pintype "bidirectional"))
      (node (ref "B04") (pin "P1") (pinfunction "P$2_P1") (pintype "bidirectional"))
    )
    (net (code "65") (name "/I{slash}~{O_BMB_06}") (class "Default")
      (node (ref "B01") (pin "D2") (pinfunction "P$2_D2") (pintype "bidirectional"))
      (node (ref "B02") (pin "D2") (pinfunction "P$2_D2") (pintype "bidirectional"))
      (node (ref "B03") (pin "D2") (pinfunction "P$2_D2") (pintype "bidirectional"))
      (node (ref "B04") (pin "D2") (pinfunction "P$2_D2") (pintype "bidirectional"))
    )
    (net (code "66") (name "/I{slash}~{O_BMB_07}") (class "Default")
      (node (ref "B01") (pin "H2") (pinfunction "P$2_H2") (pintype "bidirectional"))
      (node (ref "B02") (pin "H2") (pinfunction "P$2_H2") (pintype "bidirectional"))
      (node (ref "B03") (pin "H2") (pinfunction "P$2_H2") (pintype "bidirectional"))
      (node (ref "B04") (pin "H2") (pinfunction "P$2_H2") (pintype "bidirectional"))
    )
    (net (code "67") (name "/I{slash}~{O_BMB_08}") (class "Default")
      (node (ref "B01") (pin "M2") (pinfunction "P$2_M2") (pintype "bidirectional"))
      (node (ref "B02") (pin "M2") (pinfunction "P$2_M2") (pintype "bidirectional"))
      (node (ref "B03") (pin "M2") (pinfunction "P$2_M2") (pintype "bidirectional"))
      (node (ref "B04") (pin "M2") (pinfunction "P$2_M2") (pintype "bidirectional"))
    )
    (net (code "68") (name "/I{slash}~{O_INT_RQ}") (class "Default")
      (node (ref "C01") (pin "M2") (pinfunction "P$2_M2") (pintype "bidirectional"))
      (node (ref "C02") (pin "M2") (pinfunction "P$2_M2") (pintype "bidirectional"))
      (node (ref "C03") (pin "M2") (pinfunction "P$2_M2") (pintype "bidirectional"))
      (node (ref "C04") (pin "M2") (pinfunction "P$2_M2") (pintype "bidirectional"))
    )
    (net (code "69") (name "/I{slash}~{O_SKP_RQ}") (class "Default")
      (node (ref "C01") (pin "K2") (pinfunction "P$2_K2") (pintype "bidirectional"))
      (node (ref "C02") (pin "K2") (pinfunction "P$2_K2") (pintype "bidirectional"))
      (node (ref "C03") (pin "K2") (pinfunction "P$2_K2") (pintype "bidirectional"))
      (node (ref "C04") (pin "K2") (pinfunction "P$2_K2") (pintype "bidirectional"))
    )
    (net (code "70") (name "/~{IM_00}") (class "Default")
      (node (ref "C01") (pin "B1") (pinfunction "P$2_B1") (pintype "bidirectional"))
      (node (ref "C02") (pin "B1") (pinfunction "P$2_B1") (pintype "bidirectional"))
      (node (ref "C03") (pin "B1") (pinfunction "P$2_B1") (pintype "bidirectional"))
      (node (ref "C04") (pin "B1") (pinfunction "P$2_B1") (pintype "bidirectional"))
    )
    (net (code "71") (name "/~{IM_01}") (class "Default")
      (node (ref "C01") (pin "D1") (pinfunction "P$2_D1") (pintype "bidirectional"))
      (node (ref "C02") (pin "D1") (pinfunction "P$2_D1") (pintype "bidirectional"))
      (node (ref "C03") (pin "D1") (pinfunction "P$2_D1") (pintype "bidirectional"))
      (node (ref "C04") (pin "D1") (pinfunction "P$2_D1") (pintype "bidirectional"))
    )
    (net (code "72") (name "/~{IM_02}") (class "Default")
      (node (ref "C01") (pin "E1") (pinfunction "P$2_E1") (pintype "bidirectional"))
      (node (ref "C02") (pin "E1") (pinfunction "P$2_E1") (pintype "bidirectional"))
      (node (ref "C03") (pin "E1") (pinfunction "P$2_E1") (pintype "bidirectional"))
      (node (ref "C04") (pin "E1") (pinfunction "P$2_E1") (pintype "bidirectional"))
    )
    (net (code "73") (name "/~{IM_03}") (class "Default")
      (node (ref "C01") (pin "H1") (pinfunction "P$2_H1") (pintype "bidirectional"))
      (node (ref "C02") (pin "H1") (pinfunction "P$2_H1") (pintype "bidirectional"))
      (node (ref "C03") (pin "H1") (pinfunction "P$2_H1") (pintype "bidirectional"))
      (node (ref "C04") (pin "H1") (pinfunction "P$2_H1") (pintype "bidirectional"))
    )
    (net (code "74") (name "/~{IM_04}") (class "Default")
      (node (ref "C01") (pin "J1") (pinfunction "P$2_J1") (pintype "bidirectional"))
      (node (ref "C02") (pin "J1") (pinfunction "P$2_J1") (pintype "bidirectional"))
      (node (ref "C03") (pin "J1") (pinfunction "P$2_J1") (pintype "bidirectional"))
      (node (ref "C04") (pin "J1") (pinfunction "P$2_J1") (pintype "bidirectional"))
    )
    (net (code "75") (name "/~{IM_05}") (class "Default")
      (node (ref "C01") (pin "L1") (pinfunction "P$2_L1") (pintype "bidirectional"))
      (node (ref "C02") (pin "L1") (pinfunction "P$2_L1") (pintype "bidirectional"))
      (node (ref "C03") (pin "L1") (pinfunction "P$2_L1") (pintype "bidirectional"))
      (node (ref "C04") (pin "L1") (pinfunction "P$2_L1") (pintype "bidirectional"))
    )
    (net (code "76") (name "/~{IM_06}") (class "Default")
      (node (ref "C01") (pin "M1") (pinfunction "P$2_M1") (pintype "bidirectional"))
      (node (ref "C02") (pin "M1") (pinfunction "P$2_M1") (pintype "bidirectional"))
      (node (ref "C03") (pin "M1") (pinfunction "P$2_M1") (pintype "bidirectional"))
      (node (ref "C04") (pin "M1") (pinfunction "P$2_M1") (pintype "bidirectional"))
    )
    (net (code "77") (name "/~{IM_07}") (class "Default")
      (node (ref "C01") (pin "P1") (pinfunction "P$2_P1") (pintype "bidirectional"))
      (node (ref "C02") (pin "P1") (pinfunction "P$2_P1") (pintype "bidirectional"))
      (node (ref "C03") (pin "P1") (pinfunction "P$2_P1") (pintype "bidirectional"))
      (node (ref "C04") (pin "P1") (pinfunction "P$2_P1") (pintype "bidirectional"))
    )
    (net (code "78") (name "/~{IM_08}") (class "Default")
      (node (ref "C01") (pin "S1") (pinfunction "P$2_S1") (pintype "bidirectional"))
      (node (ref "C02") (pin "S1") (pinfunction "P$2_S1") (pintype "bidirectional"))
      (node (ref "C03") (pin "S1") (pinfunction "P$2_S1") (pintype "bidirectional"))
      (node (ref "C04") (pin "S1") (pinfunction "P$2_S1") (pintype "bidirectional"))
    )
    (net (code "79") (name "/~{IM_09}") (class "Default")
      (node (ref "C01") (pin "D2") (pinfunction "P$2_D2") (pintype "bidirectional"))
      (node (ref "C02") (pin "D2") (pinfunction "P$2_D2") (pintype "bidirectional"))
      (node (ref "C03") (pin "D2") (pinfunction "P$2_D2") (pintype "bidirectional"))
      (node (ref "C04") (pin "D2") (pinfunction "P$2_D2") (pintype "bidirectional"))
    )
    (net (code "80") (name "/~{IM_10}") (class "Default")
      (node (ref "C01") (pin "E2") (pinfunction "P$2_E2") (pintype "bidirectional"))
      (node (ref "C02") (pin "E2") (pinfunction "P$2_E2") (pintype "bidirectional"))
      (node (ref "C03") (pin "E2") (pinfunction "P$2_E2") (pintype "bidirectional"))
      (node (ref "C04") (pin "E2") (pinfunction "P$2_E2") (pintype "bidirectional"))
    )
    (net (code "81") (name "/~{IM_11}") (class "Default")
      (node (ref "C01") (pin "H2") (pinfunction "P$2_H2") (pintype "bidirectional"))
      (node (ref "C02") (pin "H2") (pinfunction "P$2_H2") (pintype "bidirectional"))
      (node (ref "C03") (pin "H2") (pinfunction "P$2_H2") (pintype "bidirectional"))
      (node (ref "C04") (pin "H2") (pinfunction "P$2_H2") (pintype "bidirectional"))
    )
    (net (code "83") (name "VCC") (class "Default")
      (node (ref "A01") (pin "A2") (pinfunction "P$2_A2") (pintype "bidirectional"))
      (node (ref "A02") (pin "A2") (pinfunction "P$2_A2") (pintype "bidirectional"))
      (node (ref "A03") (pin "A2") (pinfunction "P$2_A2") (pintype "bidirectional"))
      (node (ref "A04") (pin "A2") (pinfunction "P$2_A2") (pintype "bidirectional"))
      (node (ref "B01") (pin "A2") (pinfunction "P$2_A2") (pintype "bidirectional"))
      (node (ref "B02") (pin "A2") (pinfunction "P$2_A2") (pintype "bidirectional"))
      (node (ref "B03") (pin "A2") (pinfunction "P$2_A2") (pintype "bidirectional"))
      (node (ref "B04") (pin "A2") (pinfunction "P$2_A2") (pintype "bidirectional"))
      (node (ref "C01") (pin "A2") (pinfunction "P$2_A2") (pintype "bidirectional"))
      (node (ref "C02") (pin "A2") (pinfunction "P$2_A2") (pintype "bidirectional"))
      (node (ref "C03") (pin "A2") (pinfunction "P$2_A2") (pintype "bidirectional"))
      (node (ref "C04") (pin "A2") (pinfunction "P$2_A2") (pintype "bidirectional"))
      (node (ref "D01") (pin "A2") (pinfunction "P$2_A2") (pintype "bidirectional"))
      (node (ref "D02") (pin "A2") (pinfunction "P$2_A2") (pintype "bidirectional"))
      (node (ref "D03") (pin "A2") (pinfunction "P$2_A2") (pintype "bidirectional"))
      (node (ref "D04") (pin "A2") (pinfunction "P$2_A2") (pintype "bidirectional"))
    )
  )
)
